# cyberspace-1-rom-programmer.net
KiCad netlist of a schematic drawn in EAGLE
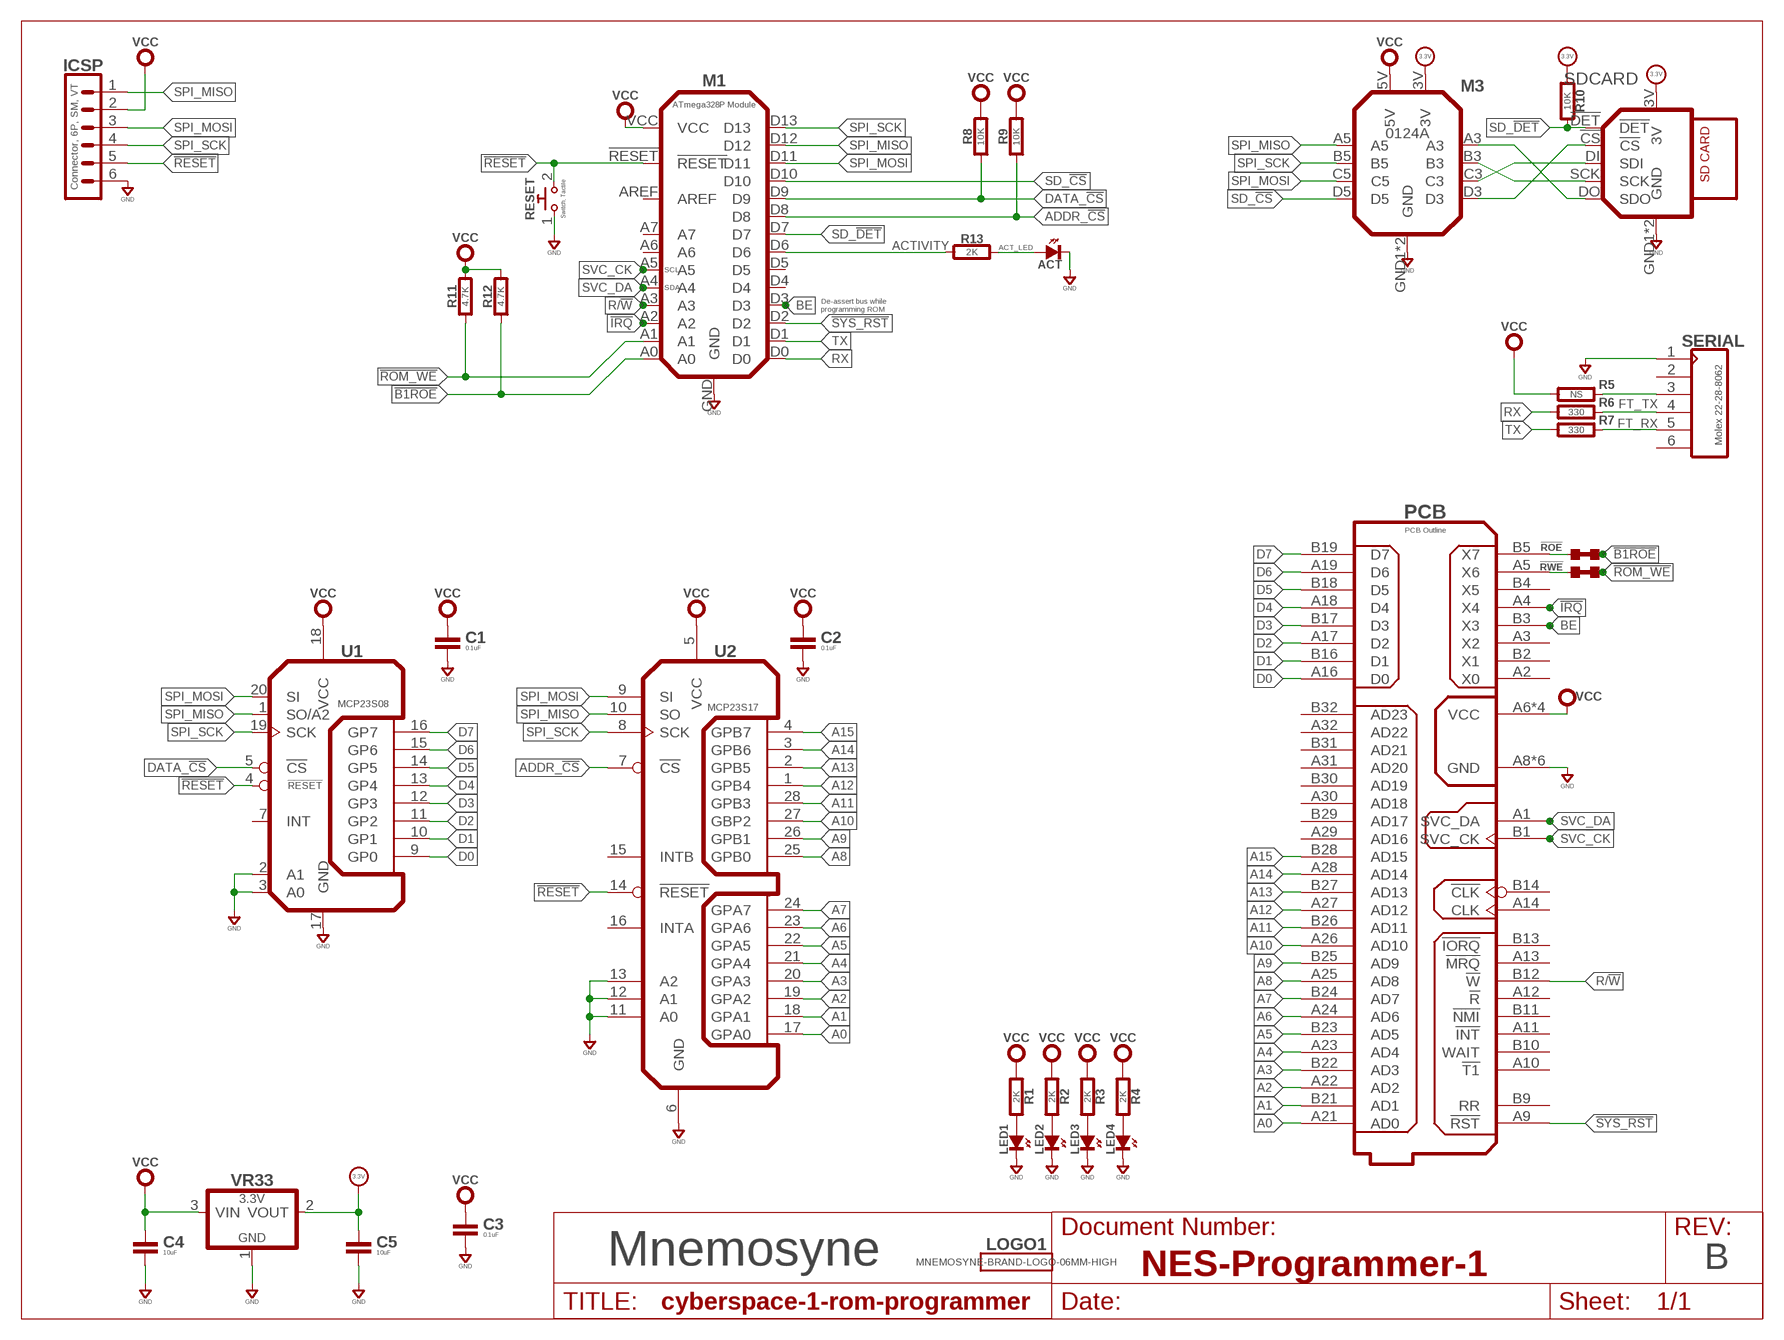
[diagram p0: schematic, sheet 1]

(export (version "E")
  (design (tool "Eeschema 10.0.6"))
  (components
    (comp (ref "!ROE")
      (value "NP")
      (footprint "eagle-import:0603-SHORT")
      (libsource (lib "eagle-import") (part "SHORT0603"))
    )
    (comp (ref "!RWE")
      (value "NP")
      (footprint "eagle-import:0603-SHORT")
      (libsource (lib "eagle-import") (part "SHORT0603"))
    )
    (comp (ref "ACT")
      (value "SMT0603")
      (footprint "eagle-import:SMD_0603")
      (libsource (lib "eagle-import") (part "SMT0603"))
    )
    (comp (ref "C1")
      (value "0.1uF")
      (footprint "eagle-import:0603-CAP")
      (libsource (lib "eagle-import") (part "CAPACITOR0603"))
    )
    (comp (ref "C2")
      (value "0.1uF")
      (footprint "eagle-import:0603-CAP")
      (libsource (lib "eagle-import") (part "CAPACITOR0603"))
    )
    (comp (ref "C3")
      (value "0.1uF")
      (footprint "eagle-import:0603-CAP")
      (libsource (lib "eagle-import") (part "CAPACITOR0603"))
    )
    (comp (ref "C4")
      (value "10uF")
      (footprint "eagle-import:0603-CAP")
      (libsource (lib "eagle-import") (part "CAPACITOR0603"))
    )
    (comp (ref "C5")
      (value "10uF")
      (footprint "eagle-import:0603-CAP")
      (libsource (lib "eagle-import") (part "CAPACITOR0603"))
    )
    (comp (ref "ICSP")
      (value "Connector, 6P, SM, VT")
      (footprint "eagle-import:BM06B-SRSS-TB")
      (fields (field (name "MFR") "JST") (field (name "MPN") "BM06-SRSS-TB"))
      (libsource (lib "eagle-import") (part "06P-SM-VT-SMT"))
    )
    (comp (ref "LED1")
      (value "SMT0603")
      (footprint "eagle-import:SMD_0603")
      (libsource (lib "eagle-import") (part "SMT0603"))
    )
    (comp (ref "LED2")
      (value "SMT0603")
      (footprint "eagle-import:SMD_0603")
      (libsource (lib "eagle-import") (part "SMT0603"))
    )
    (comp (ref "LED3")
      (value "SMT0603")
      (footprint "eagle-import:SMD_0603")
      (libsource (lib "eagle-import") (part "SMT0603"))
    )
    (comp (ref "LED4")
      (value "SMT0603")
      (footprint "eagle-import:SMD_0603")
      (libsource (lib "eagle-import") (part "SMT0603"))
    )
    (comp (ref "LOGO1")
      (value "MNEMOSYNE-BRAND-LOGO-06MM-HIGH")
      (footprint "eagle-import:MNEMOSYNE-06MM")
      (libsource (lib "eagle-import") (part "MNEMOSYNE-BRAND-LOGO-06MM-HIGH"))
    )
    (comp (ref "M1")
      (value "ATmega328P Module")
      (footprint "eagle-import:0119A")
      (fields (field (name "MFR") "Circuit Monkey") (field (name "MPN") "0119A"))
      (libsource (lib "eagle-import") (part "0119REV-A"))
    )
    (comp (ref "M3")
      (value "0124A")
      (footprint "eagle-import:0124A")
      (fields (field (name "MFR") "Circuit Monkey"))
      (libsource (lib "eagle-import") (part "0124REV-A"))
    )
    (comp (ref "PCB")
      (value "PCB Outline")
      (footprint "eagle-import:CYBERSPACE-CARD-TYPE-1A")
      (libsource (lib "eagle-import") (part "CYBERSPACE-1-CARD-1A"))
    )
    (comp (ref "R1")
      (value "2K")
      (footprint "eagle-import:0603-RES")
      (libsource (lib "eagle-import") (part "RESISTOR0603"))
    )
    (comp (ref "R2")
      (value "2K")
      (footprint "eagle-import:0603-RES")
      (libsource (lib "eagle-import") (part "RESISTOR0603"))
    )
    (comp (ref "R3")
      (value "2K")
      (footprint "eagle-import:0603-RES")
      (libsource (lib "eagle-import") (part "RESISTOR0603"))
    )
    (comp (ref "R4")
      (value "2K")
      (footprint "eagle-import:0603-RES")
      (libsource (lib "eagle-import") (part "RESISTOR0603"))
    )
    (comp (ref "R5")
      (value "NS")
      (footprint "eagle-import:0603-RES")
      (libsource (lib "eagle-import") (part "RESISTOR0603"))
    )
    (comp (ref "R6")
      (value "330")
      (footprint "eagle-import:0603-RES")
      (libsource (lib "eagle-import") (part "RESISTOR0603"))
    )
    (comp (ref "R7")
      (value "330")
      (footprint "eagle-import:0603-RES")
      (libsource (lib "eagle-import") (part "RESISTOR0603"))
    )
    (comp (ref "R8")
      (value "10K")
      (footprint "eagle-import:0603-RES")
      (libsource (lib "eagle-import") (part "RESISTOR0603"))
    )
    (comp (ref "R9")
      (value "10K")
      (footprint "eagle-import:0603-RES")
      (libsource (lib "eagle-import") (part "RESISTOR0603"))
    )
    (comp (ref "R10")
      (value "10K")
      (footprint "eagle-import:0603-RES")
      (libsource (lib "eagle-import") (part "RESISTOR0603"))
    )
    (comp (ref "R11")
      (value "4.7K")
      (footprint "eagle-import:0603-RES")
      (libsource (lib "eagle-import") (part "RESISTOR0603"))
    )
    (comp (ref "R12")
      (value "4.7K")
      (footprint "eagle-import:0603-RES")
      (libsource (lib "eagle-import") (part "RESISTOR0603"))
    )
    (comp (ref "R13")
      (value "2K")
      (footprint "eagle-import:0603-RES")
      (libsource (lib "eagle-import") (part "RESISTOR0603"))
    )
    (comp (ref "RESET")
      (value "Switch, Tactile")
      (footprint "eagle-import:TC-0202")
      (fields (field (name "MFR") "CUI") (field (name "MPN") "TS11-674-xx"))
      (libsource (lib "eagle-import") (part "TACTILESPST-RA-6X6"))
    )
    (comp (ref "SDCARD")
      (value "0127REV-A")
      (footprint "eagle-import:0127A")
      (fields (field (name "MFR") "Circuit Monkey") (field (name "MPN") "0127"))
      (libsource (lib "eagle-import") (part "0127REV-A"))
    )
    (comp (ref "SERIAL")
      (value "Molex 22-28-8062")
      (footprint "eagle-import:MA06X1-RA-THD")
      (libsource (lib "eagle-import") (part "CON_06X1-RA"))
    )
    (comp (ref "U1")
      (value "MCP23S08")
      (footprint "eagle-import:QFN-20")
      (fields (field (name "MFR") "Microchip") (field (name "MPN") "MCP23S08-E/ML"))
      (libsource (lib "eagle-import") (part "MCP23S08-QFN"))
    )
    (comp (ref "U2")
      (value "MCP23S17")
      (footprint "eagle-import:QFN-28-6X6")
      (fields (field (name "MFR") "Microchip") (field (name "MPN") "MCP23S17-x/ML"))
      (libsource (lib "eagle-import") (part "MCP23S17-QFN"))
    )
    (comp (ref "VR33")
      (value "3.3V")
      (footprint "eagle-import:SOT-23")
      (fields (field (name "MPN") "AP2120N-3.3"))
      (libsource (lib "eagle-import") (part "LDO-3P--3.3V-SOT23"))
    )
  )
  (nets
    (net (code "1") (name "/ACTIVITY") (class "Default")
      (node (ref "M1") (pin "D6") (pinfunction "D6_D6") (pintype "bidirectional"))
      (node (ref "R13") (pin "1") (pinfunction "1_1") (pintype "passive"))
    )
    (net (code "2") (name "/ACT_LED") (class "Default")
      (node (ref "ACT") (pin "A") (pinfunction "A_A") (pintype "passive"))
      (node (ref "R13") (pin "2") (pinfunction "2_2") (pintype "passive"))
    )
    (net (code "3") (name "/ADDR_~{CS}") (class "Default")
      (node (ref "M1") (pin "D8") (pinfunction "D8_D8") (pintype "bidirectional"))
      (node (ref "R9") (pin "1") (pinfunction "1_1") (pintype "passive"))
      (node (ref "U2") (pin "7") (pinfunction "~{CS}_7") (pintype "input"))
    )
    (net (code "4") (name "/DATA_~{CS}") (class "Default")
      (node (ref "M1") (pin "D9") (pinfunction "D9_D9") (pintype "bidirectional"))
      (node (ref "R8") (pin "1") (pinfunction "1_1") (pintype "passive"))
      (node (ref "U1") (pin "5") (pinfunction "~{CS}_5") (pintype "input"))
    )
    (net (code "5") (name "/FT_RX") (class "Default")
      (node (ref "R7") (pin "1") (pinfunction "1_1") (pintype "passive"))
      (node (ref "SERIAL") (pin "5") (pinfunction "5_5") (pintype "passive"))
    )
    (net (code "6") (name "/FT_TX") (class "Default")
      (node (ref "R6") (pin "1") (pinfunction "1_1") (pintype "passive"))
      (node (ref "SERIAL") (pin "4") (pinfunction "4_4") (pintype "passive"))
    )
    (net (code "7") (name "/R{slash}~{W}") (class "Default")
      (node (ref "M1") (pin "A3") (pinfunction "A3_A3") (pintype "bidirectional"))
      (node (ref "PCB") (pin "B12") (pinfunction "~{W}_B12") (pintype "bidirectional"))
    )
    (net (code "8") (name "/SD_~{CS}") (class "Default")
      (node (ref "M1") (pin "D10") (pinfunction "D10_D10") (pintype "bidirectional"))
      (node (ref "M3") (pin "D5") (pinfunction "D5_D5") (pintype "bidirectional"))
    )
    (net (code "9") (name "/SD_~{DET}") (class "Default")
      (node (ref "M1") (pin "D7") (pinfunction "D7_D7") (pintype "bidirectional"))
      (node (ref "R10") (pin "1") (pinfunction "1_1") (pintype "passive"))
      (node (ref "SDCARD") (pin "!DET") (pinfunction "~{DET}_!DET") (pintype "bidirectional"))
    )
    (net (code "10") (name "/~{B1ROE}") (class "Default")
      (node (ref "!ROE") (pin "4") (pinfunction "2_4") (pintype "passive"))
      (node (ref "M1") (pin "A0") (pinfunction "A0_A0") (pintype "bidirectional"))
      (node (ref "R12") (pin "1") (pinfunction "1_1") (pintype "passive"))
    )
    (net (code "11") (name "/~{IRQ}") (class "Default")
      (node (ref "M1") (pin "A2") (pinfunction "A2_A2") (pintype "bidirectional"))
      (node (ref "PCB") (pin "A4") (pinfunction "X4_A4") (pintype "bidirectional"))
    )
    (net (code "12") (name "/~{RESET}") (class "Default")
      (node (ref "ICSP") (pin "5") (pinfunction "5_5") (pintype "passive"))
      (node (ref "M1") (pin "!RESET") (pinfunction "~{RESET}_!RESET") (pintype "bidirectional"))
      (node (ref "RESET") (pin "2") (pinfunction "2_2") (pintype "passive"))
      (node (ref "U1") (pin "4") (pinfunction "~{RESET}_4") (pintype "input"))
      (node (ref "U2") (pin "14") (pinfunction "~{RESET}_14") (pintype "input"))
    )
    (net (code "13") (name "/~{ROM_WE}") (class "Default")
      (node (ref "!RWE") (pin "4") (pinfunction "2_4") (pintype "passive"))
      (node (ref "M1") (pin "A1") (pinfunction "A1_A1") (pintype "bidirectional"))
      (node (ref "R11") (pin "1") (pinfunction "1_1") (pintype "passive"))
    )
    (net (code "14") (name "/~{SYS_RST}") (class "Default")
      (node (ref "M1") (pin "D2") (pinfunction "D2_D2") (pintype "bidirectional"))
      (node (ref "PCB") (pin "A9") (pinfunction "~{RST}_A9") (pintype "bidirectional"))
    )
    (net (code "15") (name "3.3V") (class "Default")
      (node (ref "C5") (pin "1") (pinfunction "1_1") (pintype "passive"))
      (node (ref "M3") (pin "3V") (pinfunction "3V_3V") (pintype "bidirectional"))
      (node (ref "R10") (pin "2") (pinfunction "2_2") (pintype "passive"))
      (node (ref "SDCARD") (pin "3V") (pinfunction "3V_3V") (pintype "bidirectional"))
      (node (ref "VR33") (pin "2") (pinfunction "VOUT_2") (pintype "power_in"))
    )
    (net (code "16") (name "A0") (class "Default")
      (node (ref "PCB") (pin "A21") (pinfunction "AD0_A21") (pintype "bidirectional"))
      (node (ref "U2") (pin "17") (pinfunction "GPA0_17") (pintype "bidirectional"))
    )
    (net (code "17") (name "A1") (class "Default")
      (node (ref "PCB") (pin "B21") (pinfunction "AD1_B21") (pintype "bidirectional"))
      (node (ref "U2") (pin "18") (pinfunction "GPA1_18") (pintype "bidirectional"))
    )
    (net (code "18") (name "A2") (class "Default")
      (node (ref "PCB") (pin "A22") (pinfunction "AD2_A22") (pintype "bidirectional"))
      (node (ref "U2") (pin "19") (pinfunction "GPA2_19") (pintype "bidirectional"))
    )
    (net (code "19") (name "A3") (class "Default")
      (node (ref "PCB") (pin "B22") (pinfunction "AD3_B22") (pintype "bidirectional"))
      (node (ref "U2") (pin "20") (pinfunction "GPA3_20") (pintype "bidirectional"))
    )
    (net (code "20") (name "A4") (class "Default")
      (node (ref "PCB") (pin "A23") (pinfunction "AD4_A23") (pintype "bidirectional"))
      (node (ref "U2") (pin "21") (pinfunction "GPA4_21") (pintype "bidirectional"))
    )
    (net (code "21") (name "A5") (class "Default")
      (node (ref "PCB") (pin "B23") (pinfunction "AD5_B23") (pintype "bidirectional"))
      (node (ref "U2") (pin "22") (pinfunction "GPA5_22") (pintype "bidirectional"))
    )
    (net (code "22") (name "A6") (class "Default")
      (node (ref "PCB") (pin "A24") (pinfunction "AD6_A24") (pintype "bidirectional"))
      (node (ref "U2") (pin "23") (pinfunction "GPA6_23") (pintype "bidirectional"))
    )
    (net (code "23") (name "A7") (class "Default")
      (node (ref "PCB") (pin "B24") (pinfunction "AD7_B24") (pintype "bidirectional"))
      (node (ref "U2") (pin "24") (pinfunction "GPA7_24") (pintype "bidirectional"))
    )
    (net (code "24") (name "A8") (class "Default")
      (node (ref "PCB") (pin "A25") (pinfunction "AD8_A25") (pintype "bidirectional"))
      (node (ref "U2") (pin "25") (pinfunction "GPB0_25") (pintype "bidirectional"))
    )
    (net (code "25") (name "A9") (class "Default")
      (node (ref "PCB") (pin "B25") (pinfunction "AD9_B25") (pintype "bidirectional"))
      (node (ref "U2") (pin "26") (pinfunction "GPB1_26") (pintype "bidirectional"))
    )
    (net (code "26") (name "A10") (class "Default")
      (node (ref "PCB") (pin "A26") (pinfunction "AD10_A26") (pintype "bidirectional"))
      (node (ref "U2") (pin "27") (pinfunction "GBP2_27") (pintype "bidirectional"))
    )
    (net (code "27") (name "A11") (class "Default")
      (node (ref "PCB") (pin "B26") (pinfunction "AD11_B26") (pintype "bidirectional"))
      (node (ref "U2") (pin "28") (pinfunction "GPB3_28") (pintype "bidirectional"))
    )
    (net (code "28") (name "A12") (class "Default")
      (node (ref "PCB") (pin "A27") (pinfunction "AD12_A27") (pintype "bidirectional"))
      (node (ref "U2") (pin "1") (pinfunction "GPB4_1") (pintype "bidirectional"))
    )
    (net (code "29") (name "A13") (class "Default")
      (node (ref "PCB") (pin "B27") (pinfunction "AD13_B27") (pintype "bidirectional"))
      (node (ref "U2") (pin "2") (pinfunction "GPB5_2") (pintype "bidirectional"))
    )
    (net (code "30") (name "A14") (class "Default")
      (node (ref "PCB") (pin "A28") (pinfunction "AD14_A28") (pintype "bidirectional"))
      (node (ref "U2") (pin "3") (pinfunction "GPB6_3") (pintype "bidirectional"))
    )
    (net (code "31") (name "A15") (class "Default")
      (node (ref "PCB") (pin "B28") (pinfunction "AD15_B28") (pintype "bidirectional"))
      (node (ref "U2") (pin "4") (pinfunction "GPB7_4") (pintype "bidirectional"))
    )
    (net (code "32") (name "BE") (class "Default")
      (node (ref "M1") (pin "D3") (pinfunction "D3_D3") (pintype "bidirectional"))
      (node (ref "PCB") (pin "B3") (pinfunction "X3_B3") (pintype "bidirectional"))
    )
    (net (code "33") (name "D0") (class "Default")
      (node (ref "PCB") (pin "A16") (pinfunction "D0_A16") (pintype "bidirectional"))
      (node (ref "U1") (pin "9") (pinfunction "GP0_9") (pintype "bidirectional"))
    )
    (net (code "34") (name "D1") (class "Default")
      (node (ref "PCB") (pin "B16") (pinfunction "D1_B16") (pintype "bidirectional"))
      (node (ref "U1") (pin "10") (pinfunction "GP1_10") (pintype "bidirectional"))
    )
    (net (code "35") (name "D2") (class "Default")
      (node (ref "PCB") (pin "A17") (pinfunction "D2_A17") (pintype "bidirectional"))
      (node (ref "U1") (pin "11") (pinfunction "GP2_11") (pintype "bidirectional"))
    )
    (net (code "36") (name "D3") (class "Default")
      (node (ref "PCB") (pin "B17") (pinfunction "D3_B17") (pintype "bidirectional"))
      (node (ref "U1") (pin "12") (pinfunction "GP3_12") (pintype "bidirectional"))
    )
    (net (code "37") (name "D4") (class "Default")
      (node (ref "PCB") (pin "A18") (pinfunction "D4_A18") (pintype "bidirectional"))
      (node (ref "U1") (pin "13") (pinfunction "GP4_13") (pintype "bidirectional"))
    )
    (net (code "38") (name "D5") (class "Default")
      (node (ref "PCB") (pin "B18") (pinfunction "D5_B18") (pintype "bidirectional"))
      (node (ref "U1") (pin "14") (pinfunction "GP5_14") (pintype "bidirectional"))
    )
    (net (code "39") (name "D6") (class "Default")
      (node (ref "PCB") (pin "A19") (pinfunction "D6_A19") (pintype "bidirectional"))
      (node (ref "U1") (pin "15") (pinfunction "GP6_15") (pintype "bidirectional"))
    )
    (net (code "40") (name "D7") (class "Default")
      (node (ref "PCB") (pin "B19") (pinfunction "D7_B19") (pintype "bidirectional"))
      (node (ref "U1") (pin "16") (pinfunction "GP7_16") (pintype "bidirectional"))
    )
    (net (code "41") (name "GND") (class "Default")
      (node (ref "ACT") (pin "K") (pinfunction "C_K") (pintype "passive"))
      (node (ref "C1") (pin "2") (pinfunction "2_2") (pintype "passive"))
      (node (ref "C2") (pin "2") (pinfunction "2_2") (pintype "passive"))
      (node (ref "C3") (pin "2") (pinfunction "2_2") (pintype "passive"))
      (node (ref "C4") (pin "2") (pinfunction "2_2") (pintype "passive"))
      (node (ref "C5") (pin "2") (pinfunction "2_2") (pintype "passive"))
      (node (ref "ICSP") (pin "6") (pinfunction "6_6") (pintype "passive"))
      (node (ref "LED1") (pin "K") (pinfunction "C_K") (pintype "passive"))
      (node (ref "LED2") (pin "K") (pinfunction "C_K") (pintype "passive"))
      (node (ref "LED3") (pin "K") (pinfunction "C_K") (pintype "passive"))
      (node (ref "LED4") (pin "K") (pinfunction "C_K") (pintype "passive"))
      (node (ref "M1") (pin "GND") (pinfunction "GND_GND") (pintype "bidirectional"))
      (node (ref "M3") (pin "GND1") (pinfunction "GND_GND1") (pintype "bidirectional"))
      (node (ref "M3") (pin "GND2") (pinfunction "GND_GND2") (pintype "bidirectional"))
      (node (ref "PCB") (pin "A15") (pinfunction "GND_A15") (pintype "power_in"))
      (node (ref "PCB") (pin "A20") (pinfunction "GND_A20") (pintype "power_in"))
      (node (ref "PCB") (pin "A8") (pinfunction "GND_A8") (pintype "power_in"))
      (node (ref "PCB") (pin "B15") (pinfunction "GND_B15") (pintype "power_in"))
      (node (ref "PCB") (pin "B20") (pinfunction "GND_B20") (pintype "power_in"))
      (node (ref "PCB") (pin "B8") (pinfunction "GND_B8") (pintype "power_in"))
      (node (ref "RESET") (pin "1") (pinfunction "1_1") (pintype "passive"))
      (node (ref "SDCARD") (pin "GND1") (pinfunction "GND_GND1") (pintype "bidirectional"))
      (node (ref "SDCARD") (pin "GND2") (pinfunction "GND_GND2") (pintype "bidirectional"))
      (node (ref "SERIAL") (pin "1") (pinfunction "1_1") (pintype "passive"))
      (node (ref "U1") (pin "17") (pinfunction "GND_17") (pintype "power_in"))
      (node (ref "U1") (pin "2") (pinfunction "A1_2") (pintype "input"))
      (node (ref "U1") (pin "3") (pinfunction "A0_3") (pintype "input"))
      (node (ref "U2") (pin "11") (pinfunction "A0_11") (pintype "input"))
      (node (ref "U2") (pin "12") (pinfunction "A1_12") (pintype "input"))
      (node (ref "U2") (pin "13") (pinfunction "A2_13") (pintype "input"))
      (node (ref "U2") (pin "6") (pinfunction "GND_6") (pintype "power_in"))
      (node (ref "VR33") (pin "1") (pinfunction "GND_1") (pintype "power_in"))
    )
    (net (code "42") (name "Net-(!ROE-1)") (class "Default")
      (node (ref "!ROE") (pin "3") (pinfunction "1_3") (pintype "passive"))
      (node (ref "PCB") (pin "B5") (pinfunction "X7_B5") (pintype "bidirectional"))
    )
    (net (code "43") (name "Net-(!RWE-1)") (class "Default")
      (node (ref "!RWE") (pin "3") (pinfunction "1_3") (pintype "passive"))
      (node (ref "PCB") (pin "A5") (pinfunction "X6_A5") (pintype "bidirectional"))
    )
    (net (code "44") (name "Net-(LED1-PadA)") (class "Default")
      (node (ref "LED1") (pin "A") (pinfunction "A_A") (pintype "passive"))
      (node (ref "R1") (pin "2") (pinfunction "2_2") (pintype "passive"))
    )
    (net (code "45") (name "Net-(LED2-PadA)") (class "Default")
      (node (ref "LED2") (pin "A") (pinfunction "A_A") (pintype "passive"))
      (node (ref "R2") (pin "2") (pinfunction "2_2") (pintype "passive"))
    )
    (net (code "46") (name "Net-(LED3-PadA)") (class "Default")
      (node (ref "LED3") (pin "A") (pinfunction "A_A") (pintype "passive"))
      (node (ref "R3") (pin "2") (pinfunction "2_2") (pintype "passive"))
    )
    (net (code "47") (name "Net-(LED4-PadA)") (class "Default")
      (node (ref "LED4") (pin "A") (pinfunction "A_A") (pintype "passive"))
      (node (ref "R4") (pin "2") (pinfunction "2_2") (pintype "passive"))
    )
    (net (code "48") (name "Net-(M3-PadB3)") (class "Default")
      (node (ref "M3") (pin "B3") (pinfunction "B3_B3") (pintype "bidirectional"))
      (node (ref "SDCARD") (pin "SCK") (pinfunction "SCK_SCK") (pintype "bidirectional"))
    )
    (net (code "49") (name "Net-(R5-Pad1)") (class "Default")
      (node (ref "R5") (pin "1") (pinfunction "1_1") (pintype "passive"))
      (node (ref "SERIAL") (pin "3") (pinfunction "3_3") (pintype "passive"))
    )
    (net (code "50") (name "Net-(SDCARD-SDI)") (class "Default")
      (node (ref "M3") (pin "C3") (pinfunction "C3_C3") (pintype "bidirectional"))
      (node (ref "SDCARD") (pin "DI") (pinfunction "SDI_DI") (pintype "bidirectional"))
    )
    (net (code "51") (name "Net-(SDCARD-SDO)") (class "Default")
      (node (ref "M3") (pin "A3") (pinfunction "A3_A3") (pintype "bidirectional"))
      (node (ref "SDCARD") (pin "DO") (pinfunction "SDO_DO") (pintype "bidirectional"))
    )
    (net (code "52") (name "Net-(SDCARD-~{CS})") (class "Default")
      (node (ref "M3") (pin "D3") (pinfunction "D3_D3") (pintype "bidirectional"))
      (node (ref "SDCARD") (pin "!CS") (pinfunction "~{CS}_!CS") (pintype "bidirectional"))
    )
    (net (code "53") (name "RX") (class "Default")
      (node (ref "M1") (pin "D0") (pinfunction "D0_D0") (pintype "bidirectional"))
      (node (ref "R6") (pin "2") (pinfunction "2_2") (pintype "passive"))
    )
    (net (code "54") (name "SPI_MISO") (class "Default")
      (node (ref "ICSP") (pin "1") (pinfunction "1_1") (pintype "passive"))
      (node (ref "M1") (pin "D12") (pinfunction "D12_D12") (pintype "bidirectional"))
      (node (ref "M3") (pin "A5") (pinfunction "A5_A5") (pintype "bidirectional"))
      (node (ref "U1") (pin "1") (pinfunction "SO/A2_1") (pintype "input"))
      (node (ref "U2") (pin "10") (pinfunction "SO_10") (pintype "output"))
    )
    (net (code "55") (name "SPI_MOSI") (class "Default")
      (node (ref "ICSP") (pin "3") (pinfunction "3_3") (pintype "passive"))
      (node (ref "M1") (pin "D11") (pinfunction "D11_D11") (pintype "bidirectional"))
      (node (ref "M3") (pin "C5") (pinfunction "C5_C5") (pintype "bidirectional"))
      (node (ref "U1") (pin "20") (pinfunction "SI_20") (pintype "input"))
      (node (ref "U2") (pin "9") (pinfunction "SI_9") (pintype "input"))
    )
    (net (code "56") (name "SPI_SCK") (class "Default")
      (node (ref "ICSP") (pin "4") (pinfunction "4_4") (pintype "passive"))
      (node (ref "M1") (pin "D13") (pinfunction "D13_D13") (pintype "bidirectional"))
      (node (ref "M3") (pin "B5") (pinfunction "B5_B5") (pintype "bidirectional"))
      (node (ref "U1") (pin "19") (pinfunction "SCK_19") (pintype "input"))
      (node (ref "U2") (pin "8") (pinfunction "SCK_8") (pintype "input"))
    )
    (net (code "57") (name "SVC_CK") (class "Default")
      (node (ref "M1") (pin "A5") (pinfunction "A5_A5") (pintype "bidirectional"))
      (node (ref "PCB") (pin "B1") (pinfunction "SVC_CK_B1") (pintype "bidirectional"))
    )
    (net (code "58") (name "SVC_DA") (class "Default")
      (node (ref "M1") (pin "A4") (pinfunction "A4_A4") (pintype "bidirectional"))
      (node (ref "PCB") (pin "A1") (pinfunction "SVC_DA_A1") (pintype "bidirectional"))
    )
    (net (code "59") (name "TX") (class "Default")
      (node (ref "M1") (pin "D1") (pinfunction "D1_D1") (pintype "bidirectional"))
      (node (ref "R7") (pin "2") (pinfunction "2_2") (pintype "passive"))
    )
    (net (code "60") (name "VCC") (class "Default")
      (node (ref "C1") (pin "1") (pinfunction "1_1") (pintype "passive"))
      (node (ref "C2") (pin "1") (pinfunction "1_1") (pintype "passive"))
      (node (ref "C3") (pin "1") (pinfunction "1_1") (pintype "passive"))
      (node (ref "C4") (pin "1") (pinfunction "1_1") (pintype "passive"))
      (node (ref "ICSP") (pin "2") (pinfunction "2_2") (pintype "passive"))
      (node (ref "M1") (pin "VCC") (pinfunction "VCC_VCC") (pintype "bidirectional"))
      (node (ref "M3") (pin "5V") (pinfunction "5V_5V") (pintype "bidirectional"))
      (node (ref "PCB") (pin "A6") (pinfunction "VCC_A6") (pintype "power_in"))
      (node (ref "PCB") (pin "A7") (pinfunction "VCC_A7") (pintype "power_in"))
      (node (ref "PCB") (pin "B6") (pinfunction "VCC_B6") (pintype "power_in"))
      (node (ref "PCB") (pin "B7") (pinfunction "VCC_B7") (pintype "power_in"))
      (node (ref "R1") (pin "1") (pinfunction "1_1") (pintype "passive"))
      (node (ref "R11") (pin "2") (pinfunction "2_2") (pintype "passive"))
      (node (ref "R12") (pin "2") (pinfunction "2_2") (pintype "passive"))
      (node (ref "R2") (pin "1") (pinfunction "1_1") (pintype "passive"))
      (node (ref "R3") (pin "1") (pinfunction "1_1") (pintype "passive"))
      (node (ref "R4") (pin "1") (pinfunction "1_1") (pintype "passive"))
      (node (ref "R5") (pin "2") (pinfunction "2_2") (pintype "passive"))
      (node (ref "R8") (pin "2") (pinfunction "2_2") (pintype "passive"))
      (node (ref "R9") (pin "2") (pinfunction "2_2") (pintype "passive"))
      (node (ref "U1") (pin "18") (pinfunction "VCC_18") (pintype "power_in"))
      (node (ref "U2") (pin "5") (pinfunction "VCC_5") (pintype "power_in"))
      (node (ref "VR33") (pin "3") (pinfunction "VIN_3") (pintype "power_in"))
    )
    (net (code "61") (name "unconnected-(M1-PadA6)") (class "Default")
      (node (ref "M1") (pin "A6") (pinfunction "A6_A6") (pintype "bidirectional"))
    )
    (net (code "62") (name "unconnected-(M1-PadA7)") (class "Default")
      (node (ref "M1") (pin "A7") (pinfunction "A7_A7") (pintype "bidirectional"))
    )
    (net (code "63") (name "unconnected-(M1-PadAREF)") (class "Default")
      (node (ref "M1") (pin "AREF") (pinfunction "AREF_AREF") (pintype "bidirectional"))
    )
    (net (code "64") (name "unconnected-(M1-PadD4)") (class "Default")
      (node (ref "M1") (pin "D4") (pinfunction "D4_D4") (pintype "bidirectional"))
    )
    (net (code "65") (name "unconnected-(M1-PadD5)") (class "Default")
      (node (ref "M1") (pin "D5") (pinfunction "D5_D5") (pintype "bidirectional"))
    )
    (net (code "66") (name "unconnected-(PCB-AD16-PadA29)") (class "Default")
      (node (ref "PCB") (pin "A29") (pinfunction "AD16_A29") (pintype "bidirectional"))
    )
    (net (code "67") (name "unconnected-(PCB-AD17-PadB29)") (class "Default")
      (node (ref "PCB") (pin "B29") (pinfunction "AD17_B29") (pintype "bidirectional"))
    )
    (net (code "68") (name "unconnected-(PCB-AD18-PadA30)") (class "Default")
      (node (ref "PCB") (pin "A30") (pinfunction "AD18_A30") (pintype "bidirectional"))
    )
    (net (code "69") (name "unconnected-(PCB-AD19-PadB30)") (class "Default")
      (node (ref "PCB") (pin "B30") (pinfunction "AD19_B30") (pintype "bidirectional"))
    )
    (net (code "70") (name "unconnected-(PCB-AD20-PadA31)") (class "Default")
      (node (ref "PCB") (pin "A31") (pinfunction "AD20_A31") (pintype "bidirectional"))
    )
    (net (code "71") (name "unconnected-(PCB-AD21-PadB31)") (class "Default")
      (node (ref "PCB") (pin "B31") (pinfunction "AD21_B31") (pintype "bidirectional"))
    )
    (net (code "72") (name "unconnected-(PCB-AD22-PadA32)") (class "Default")
      (node (ref "PCB") (pin "A32") (pinfunction "AD22_A32") (pintype "bidirectional"))
    )
    (net (code "73") (name "unconnected-(PCB-AD23-PadB32)") (class "Default")
      (node (ref "PCB") (pin "B32") (pinfunction "AD23_B32") (pintype "bidirectional"))
    )
    (net (code "74") (name "unconnected-(PCB-CLK-PadA14)") (class "Default")
      (node (ref "PCB") (pin "A14") (pinfunction "CLK_A14") (pintype "bidirectional"))
    )
    (net (code "75") (name "unconnected-(PCB-RR-PadB9)") (class "Default")
      (node (ref "PCB") (pin "B9") (pinfunction "RR_B9") (pintype "bidirectional"))
    )
    (net (code "76") (name "unconnected-(PCB-WAIT-PadB10)") (class "Default")
      (node (ref "PCB") (pin "B10") (pinfunction "WAIT_B10") (pintype "bidirectional"))
    )
    (net (code "77") (name "unconnected-(PCB-X0-PadA2)") (class "Default")
      (node (ref "PCB") (pin "A2") (pinfunction "X0_A2") (pintype "bidirectional"))
    )
    (net (code "78") (name "unconnected-(PCB-X1-PadB2)") (class "Default")
      (node (ref "PCB") (pin "B2") (pinfunction "X1_B2") (pintype "bidirectional"))
    )
    (net (code "79") (name "unconnected-(PCB-X2-PadA3)") (class "Default")
      (node (ref "PCB") (pin "A3") (pinfunction "X2_A3") (pintype "bidirectional"))
    )
    (net (code "80") (name "unconnected-(PCB-X5-PadB4)") (class "Default")
      (node (ref "PCB") (pin "B4") (pinfunction "X5_B4") (pintype "bidirectional"))
    )
    (net (code "81") (name "unconnected-(PCB-~{CLK}-PadB14)") (class "Default")
      (node (ref "PCB") (pin "B14") (pinfunction "~{CLK}_B14") (pintype "bidirectional"))
    )
    (net (code "82") (name "unconnected-(PCB-~{INT}-PadA11)") (class "Default")
      (node (ref "PCB") (pin "A11") (pinfunction "~{INT}_A11") (pintype "bidirectional"))
    )
    (net (code "83") (name "unconnected-(PCB-~{IORQ}-PadB13)") (class "Default")
      (node (ref "PCB") (pin "B13") (pinfunction "~{IORQ}_B13") (pintype "bidirectional"))
    )
    (net (code "84") (name "unconnected-(PCB-~{MRQ}-PadA13)") (class "Default")
      (node (ref "PCB") (pin "A13") (pinfunction "~{MRQ}_A13") (pintype "bidirectional"))
    )
    (net (code "85") (name "unconnected-(PCB-~{NMI}-PadB11)") (class "Default")
      (node (ref "PCB") (pin "B11") (pinfunction "~{NMI}_B11") (pintype "bidirectional"))
    )
    (net (code "86") (name "unconnected-(PCB-~{R}-PadA12)") (class "Default")
      (node (ref "PCB") (pin "A12") (pinfunction "~{R}_A12") (pintype "bidirectional"))
    )
    (net (code "87") (name "unconnected-(PCB-~{T1}-PadA10)") (class "Default")
      (node (ref "PCB") (pin "A10") (pinfunction "~{T1}_A10") (pintype "bidirectional"))
    )
    (net (code "88") (name "unconnected-(SERIAL-Pad2)") (class "Default")
      (node (ref "SERIAL") (pin "2") (pinfunction "2_2") (pintype "passive"))
    )
    (net (code "89") (name "unconnected-(SERIAL-Pad6)") (class "Default")
      (node (ref "SERIAL") (pin "6") (pinfunction "6_6") (pintype "passive"))
    )
    (net (code "90") (name "unconnected-(U1-INT-Pad7)") (class "Default")
      (node (ref "U1") (pin "7") (pinfunction "INT_7") (pintype "output"))
    )
    (net (code "91") (name "unconnected-(U2-INTA-Pad16)") (class "Default")
      (node (ref "U2") (pin "16") (pinfunction "INTA_16") (pintype "output"))
    )
    (net (code "92") (name "unconnected-(U2-INTB-Pad15)") (class "Default")
      (node (ref "U2") (pin "15") (pinfunction "INTB_15") (pintype "output"))
    )
  )
)
